# AE_ESP_board.net
KiCad netlist of a schematic drawn in EAGLE
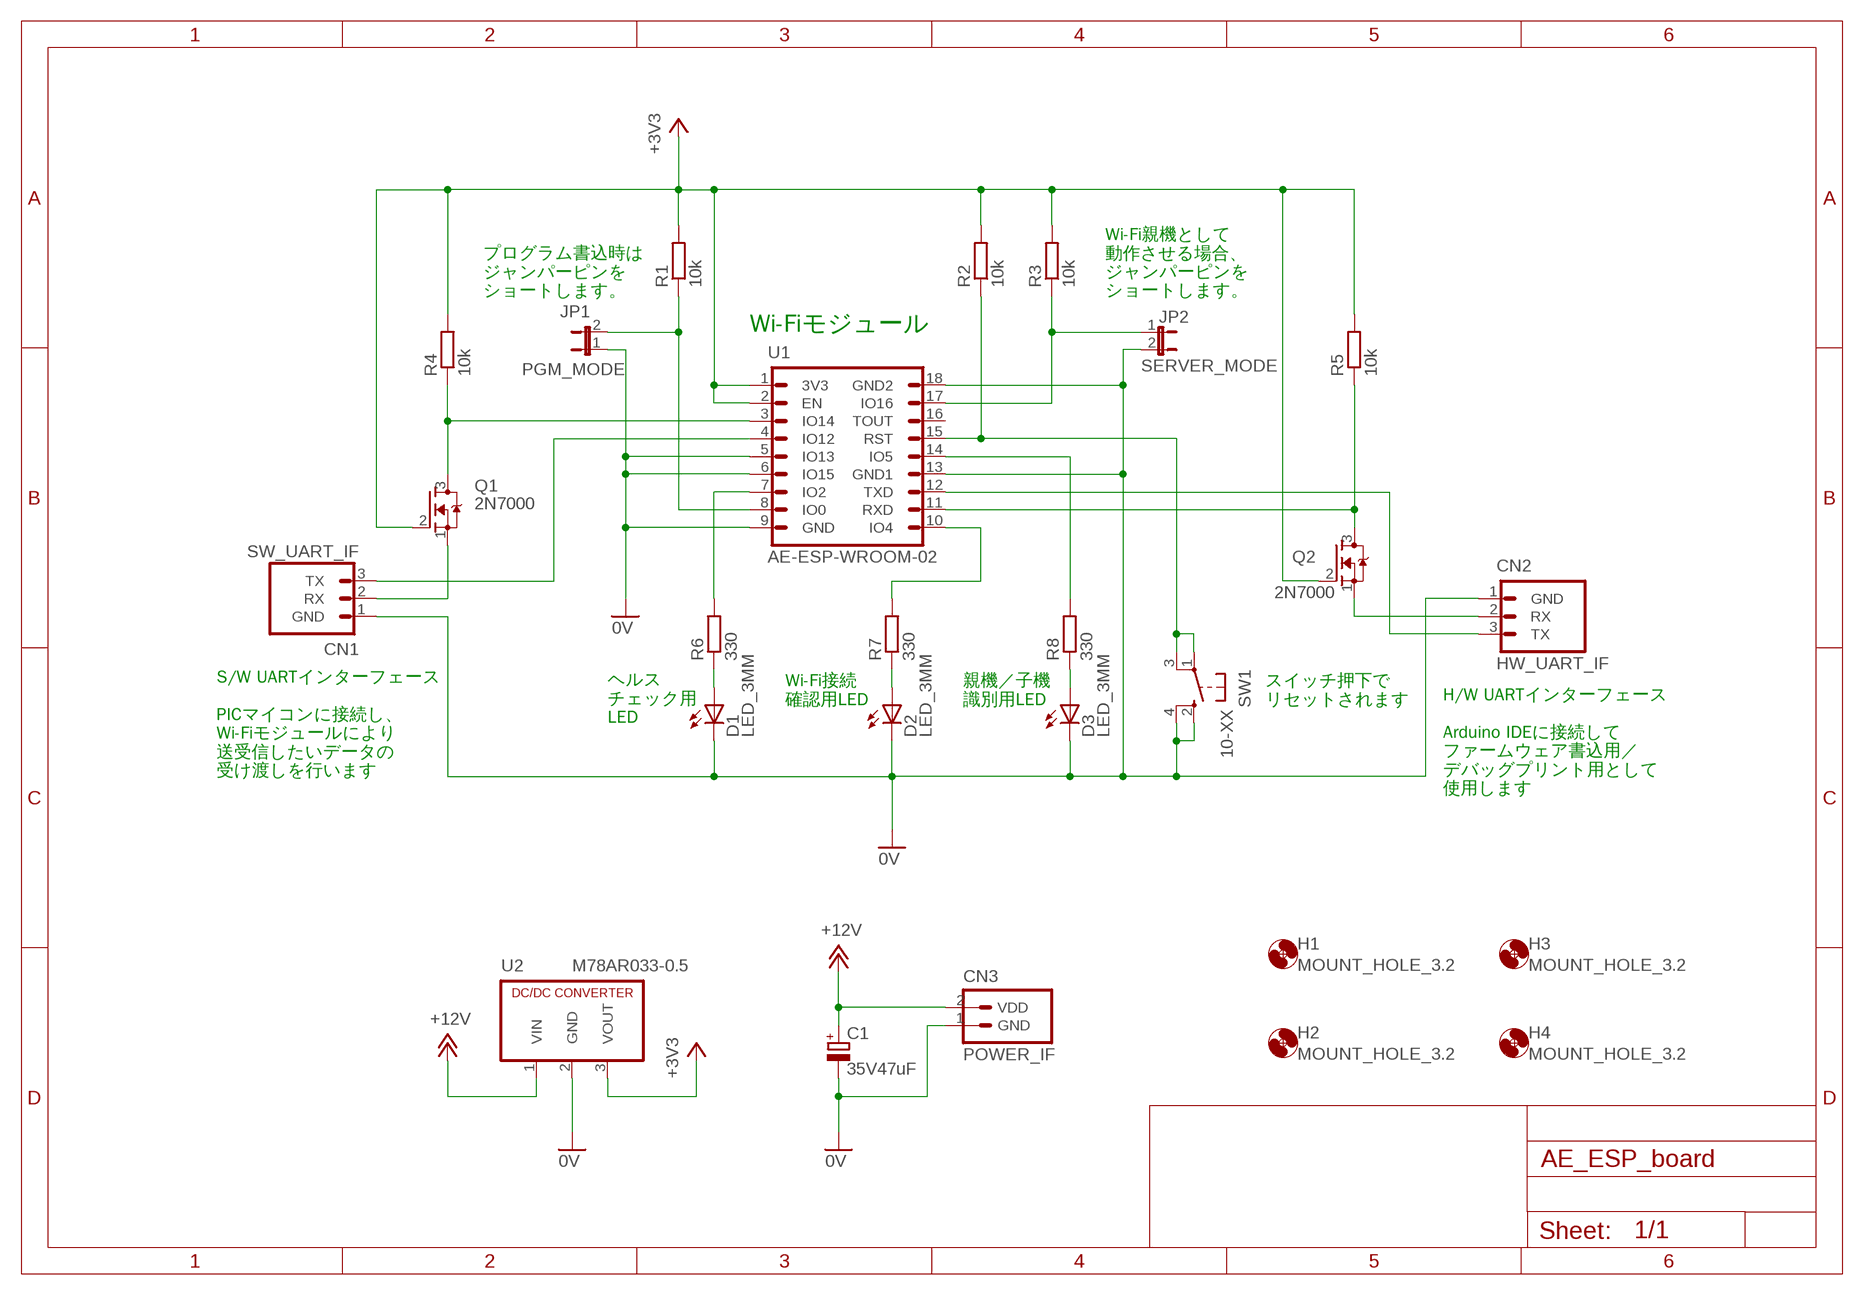
[diagram p0: schematic, sheet 1]

(export (version "E")
  (design (tool "Eeschema 10.0.6"))
  (components
    (comp (ref "C1")
      (value "35V47uF")
      (footprint "eagle-import:ELECAP_D5_100MIL")
      (libsource (lib "eagle-import") (part "ELECAP_D5_100MIL"))
    )
    (comp (ref "CN1")
      (value "SW_UART_IF")
      (footprint "eagle-import:UART_IF_3PIN")
      (libsource (lib "eagle-import") (part "UART_IF"))
    )
    (comp (ref "CN2")
      (value "HW_UART_IF")
      (footprint "eagle-import:UART_IF_3PIN")
      (libsource (lib "eagle-import") (part "UART_IF"))
    )
    (comp (ref "CN3")
      (value "POWER_IF")
      (footprint "eagle-import:HEADER_2PIN_POWER_IF")
      (libsource (lib "eagle-import") (part "POWER_IF"))
    )
    (comp (ref "D1")
      (value "LED_3MM")
      (footprint "eagle-import:LED3MM")
      (libsource (lib "eagle-import") (part "LED_3MM"))
    )
    (comp (ref "D2")
      (value "LED_3MM")
      (footprint "eagle-import:LED3MM")
      (libsource (lib "eagle-import") (part "LED_3MM"))
    )
    (comp (ref "D3")
      (value "LED_3MM")
      (footprint "eagle-import:LED3MM")
      (libsource (lib "eagle-import") (part "LED_3MM"))
    )
    (comp (ref "H1")
      (value "MOUNT_HOLE_3.2")
      (footprint "eagle-import:3,2")
      (libsource (lib "eagle-import") (part "MOUNT_HOLE_3.2"))
    )
    (comp (ref "H2")
      (value "MOUNT_HOLE_3.2")
      (footprint "eagle-import:3,2")
      (libsource (lib "eagle-import") (part "MOUNT_HOLE_3.2"))
    )
    (comp (ref "H3")
      (value "MOUNT_HOLE_3.2")
      (footprint "eagle-import:3,2")
      (libsource (lib "eagle-import") (part "MOUNT_HOLE_3.2"))
    )
    (comp (ref "H4")
      (value "MOUNT_HOLE_3.2")
      (footprint "eagle-import:3,2")
      (libsource (lib "eagle-import") (part "MOUNT_HOLE_3.2"))
    )
    (comp (ref "JP1")
      (value "PGM_MODE")
      (footprint "eagle-import:JP1")
      (libsource (lib "eagle-import") (part "JP1E"))
    )
    (comp (ref "JP2")
      (value "SERVER_MODE")
      (footprint "eagle-import:JP1")
      (libsource (lib "eagle-import") (part "JP1E"))
    )
    (comp (ref "Q1")
      (value "2N7000")
      (footprint "eagle-import:TO-92NL")
      (libsource (lib "eagle-import") (part "2N7000"))
    )
    (comp (ref "Q2")
      (value "2N7000")
      (footprint "eagle-import:TO-92NL")
      (libsource (lib "eagle-import") (part "2N7000"))
    )
    (comp (ref "R1")
      (value "10k")
      (footprint "eagle-import:RESISTOR_0204_200MIL")
      (libsource (lib "eagle-import") (part "RESISTOR_200MIL"))
    )
    (comp (ref "R2")
      (value "10k")
      (footprint "eagle-import:RESISTOR_0204_200MIL")
      (libsource (lib "eagle-import") (part "RESISTOR_200MIL"))
    )
    (comp (ref "R3")
      (value "10k")
      (footprint "eagle-import:RESISTOR_0204_200MIL")
      (libsource (lib "eagle-import") (part "RESISTOR_200MIL"))
    )
    (comp (ref "R4")
      (value "10k")
      (footprint "eagle-import:RESISTOR_0204_200MIL")
      (libsource (lib "eagle-import") (part "RESISTOR_200MIL"))
    )
    (comp (ref "R5")
      (value "10k")
      (footprint "eagle-import:RESISTOR_0204_200MIL")
      (libsource (lib "eagle-import") (part "RESISTOR_200MIL"))
    )
    (comp (ref "R6")
      (value "330")
      (footprint "eagle-import:RESISTOR_0204_200MIL")
      (libsource (lib "eagle-import") (part "RESISTOR_200MIL"))
    )
    (comp (ref "R7")
      (value "330")
      (footprint "eagle-import:RESISTOR_0204_200MIL")
      (libsource (lib "eagle-import") (part "RESISTOR_200MIL"))
    )
    (comp (ref "R8")
      (value "330")
      (footprint "eagle-import:RESISTOR_0204_200MIL")
      (libsource (lib "eagle-import") (part "RESISTOR_200MIL"))
    )
    (comp (ref "SW1")
      (value "10-XX")
      (footprint "eagle-import:B3F-10XX")
      (libsource (lib "eagle-import") (part "10-XX"))
    )
    (comp (ref "U1")
      (value "AE-ESP-WROOM-02")
      (footprint "eagle-import:DIL18_AE-ESP-WROOM-02")
      (libsource (lib "eagle-import") (part "AE-ESP-WROOM-02"))
    )
    (comp (ref "U2")
      (value "M78AR033-0.5")
      (footprint "eagle-import:SIP3")
      (libsource (lib "eagle-import") (part "M78AR033-0.5"))
    )
  )
  (nets
    (net (code "1") (name "+3V3") (class "Default")
      (node (ref "Q1") (pin "2") (pinfunction "G_2") (pintype "passive"))
      (node (ref "Q2") (pin "2") (pinfunction "G_2") (pintype "passive"))
      (node (ref "R1") (pin "2") (pinfunction "2_2") (pintype "passive"))
      (node (ref "R2") (pin "2") (pinfunction "2_2") (pintype "passive"))
      (node (ref "R3") (pin "2") (pinfunction "2_2") (pintype "passive"))
      (node (ref "R4") (pin "2") (pinfunction "2_2") (pintype "passive"))
      (node (ref "R5") (pin "2") (pinfunction "2_2") (pintype "passive"))
      (node (ref "U1") (pin "1") (pinfunction "3V3_1") (pintype "passive"))
      (node (ref "U1") (pin "2") (pinfunction "EN_2") (pintype "bidirectional"))
      (node (ref "U2") (pin "3") (pinfunction "VOUT_3") (pintype "passive"))
    )
    (net (code "2") (name "+12V") (class "Default")
      (node (ref "C1") (pin "+") (pinfunction "+_+") (pintype "passive"))
      (node (ref "CN3") (pin "2") (pinfunction "VDD_2") (pintype "passive"))
      (node (ref "U2") (pin "1") (pinfunction "VIN_1") (pintype "passive"))
    )
    (net (code "3") (name "0V") (class "Default")
      (node (ref "C1") (pin "-") (pinfunction "-_-") (pintype "passive"))
      (node (ref "CN1") (pin "1") (pinfunction "GND_1") (pintype "passive"))
      (node (ref "CN2") (pin "1") (pinfunction "GND_1") (pintype "passive"))
      (node (ref "CN3") (pin "1") (pinfunction "GND_1") (pintype "passive"))
      (node (ref "D1") (pin "K") (pinfunction "C_K") (pintype "passive"))
      (node (ref "D2") (pin "K") (pinfunction "C_K") (pintype "passive"))
      (node (ref "D3") (pin "K") (pinfunction "C_K") (pintype "passive"))
      (node (ref "JP1") (pin "1") (pinfunction "1_1") (pintype "passive"))
      (node (ref "JP2") (pin "2") (pinfunction "2_2") (pintype "passive"))
      (node (ref "SW1") (pin "2") (pinfunction "S_2") (pintype "passive"))
      (node (ref "SW1") (pin "4") (pinfunction "S1_4") (pintype "passive"))
      (node (ref "U1") (pin "13") (pinfunction "GND1_13") (pintype "passive"))
      (node (ref "U1") (pin "18") (pinfunction "GND2_18") (pintype "passive"))
      (node (ref "U1") (pin "5") (pinfunction "IO13_5") (pintype "bidirectional"))
      (node (ref "U1") (pin "6") (pinfunction "IO15_6") (pintype "bidirectional"))
      (node (ref "U1") (pin "9") (pinfunction "GND_9") (pintype "passive"))
      (node (ref "U2") (pin "2") (pinfunction "GND_2") (pintype "passive"))
    )
    (net (code "4") (name "Net-(CN1-RX)") (class "Default")
      (node (ref "CN1") (pin "2") (pinfunction "RX_2") (pintype "bidirectional"))
      (node (ref "Q1") (pin "1") (pinfunction "S_1") (pintype "passive"))
    )
    (net (code "5") (name "Net-(CN1-TX)") (class "Default")
      (node (ref "CN1") (pin "3") (pinfunction "TX_3") (pintype "bidirectional"))
      (node (ref "U1") (pin "4") (pinfunction "IO12_4") (pintype "bidirectional"))
    )
    (net (code "6") (name "Net-(CN2-RX)") (class "Default")
      (node (ref "CN2") (pin "2") (pinfunction "RX_2") (pintype "bidirectional"))
      (node (ref "Q2") (pin "1") (pinfunction "S_1") (pintype "passive"))
    )
    (net (code "7") (name "Net-(CN2-TX)") (class "Default")
      (node (ref "CN2") (pin "3") (pinfunction "TX_3") (pintype "bidirectional"))
      (node (ref "U1") (pin "12") (pinfunction "TXD_12") (pintype "bidirectional"))
    )
    (net (code "8") (name "Net-(D1-PadA)") (class "Default")
      (node (ref "D1") (pin "A") (pinfunction "A_A") (pintype "passive"))
      (node (ref "R6") (pin "1") (pinfunction "1_1") (pintype "passive"))
    )
    (net (code "9") (name "Net-(D2-PadA)") (class "Default")
      (node (ref "D2") (pin "A") (pinfunction "A_A") (pintype "passive"))
      (node (ref "R7") (pin "1") (pinfunction "1_1") (pintype "passive"))
    )
    (net (code "10") (name "Net-(D3-PadA)") (class "Default")
      (node (ref "D3") (pin "A") (pinfunction "A_A") (pintype "passive"))
      (node (ref "R8") (pin "1") (pinfunction "1_1") (pintype "passive"))
    )
    (net (code "11") (name "Net-(Q1-D)") (class "Default")
      (node (ref "Q1") (pin "3") (pinfunction "D_3") (pintype "passive"))
      (node (ref "R4") (pin "1") (pinfunction "1_1") (pintype "passive"))
      (node (ref "U1") (pin "3") (pinfunction "IO14_3") (pintype "bidirectional"))
    )
    (net (code "12") (name "Net-(Q2-D)") (class "Default")
      (node (ref "Q2") (pin "3") (pinfunction "D_3") (pintype "passive"))
      (node (ref "R5") (pin "1") (pinfunction "1_1") (pintype "passive"))
      (node (ref "U1") (pin "11") (pinfunction "RXD_11") (pintype "bidirectional"))
    )
    (net (code "13") (name "Net-(SW1-P)") (class "Default")
      (node (ref "R2") (pin "1") (pinfunction "1_1") (pintype "passive"))
      (node (ref "SW1") (pin "1") (pinfunction "P_1") (pintype "passive"))
      (node (ref "SW1") (pin "3") (pinfunction "P1_3") (pintype "passive"))
      (node (ref "U1") (pin "15") (pinfunction "RST_15") (pintype "bidirectional"))
    )
    (net (code "14") (name "Net-(U1-IO0)") (class "Default")
      (node (ref "JP1") (pin "2") (pinfunction "2_2") (pintype "passive"))
      (node (ref "R1") (pin "1") (pinfunction "1_1") (pintype "passive"))
      (node (ref "U1") (pin "8") (pinfunction "IO0_8") (pintype "bidirectional"))
    )
    (net (code "15") (name "Net-(U1-IO2)") (class "Default")
      (node (ref "R6") (pin "2") (pinfunction "2_2") (pintype "passive"))
      (node (ref "U1") (pin "7") (pinfunction "IO2_7") (pintype "bidirectional"))
    )
    (net (code "16") (name "Net-(U1-IO4)") (class "Default")
      (node (ref "R7") (pin "2") (pinfunction "2_2") (pintype "passive"))
      (node (ref "U1") (pin "10") (pinfunction "IO4_10") (pintype "bidirectional"))
    )
    (net (code "17") (name "Net-(U1-IO5)") (class "Default")
      (node (ref "R8") (pin "2") (pinfunction "2_2") (pintype "passive"))
      (node (ref "U1") (pin "14") (pinfunction "IO5_14") (pintype "bidirectional"))
    )
    (net (code "18") (name "Net-(U1-IO16)") (class "Default")
      (node (ref "JP2") (pin "1") (pinfunction "1_1") (pintype "passive"))
      (node (ref "R3") (pin "1") (pinfunction "1_1") (pintype "passive"))
      (node (ref "U1") (pin "17") (pinfunction "IO16_17") (pintype "bidirectional"))
    )
    (net (code "19") (name "unconnected-(U1-TOUT-Pad16)") (class "Default")
      (node (ref "U1") (pin "16") (pinfunction "TOUT_16") (pintype "bidirectional"))
    )
  )
)
